# Usb_Hub-EasyEdaPro_Project.net
KiCad netlist of a schematic drawn in EasyEDA Pro
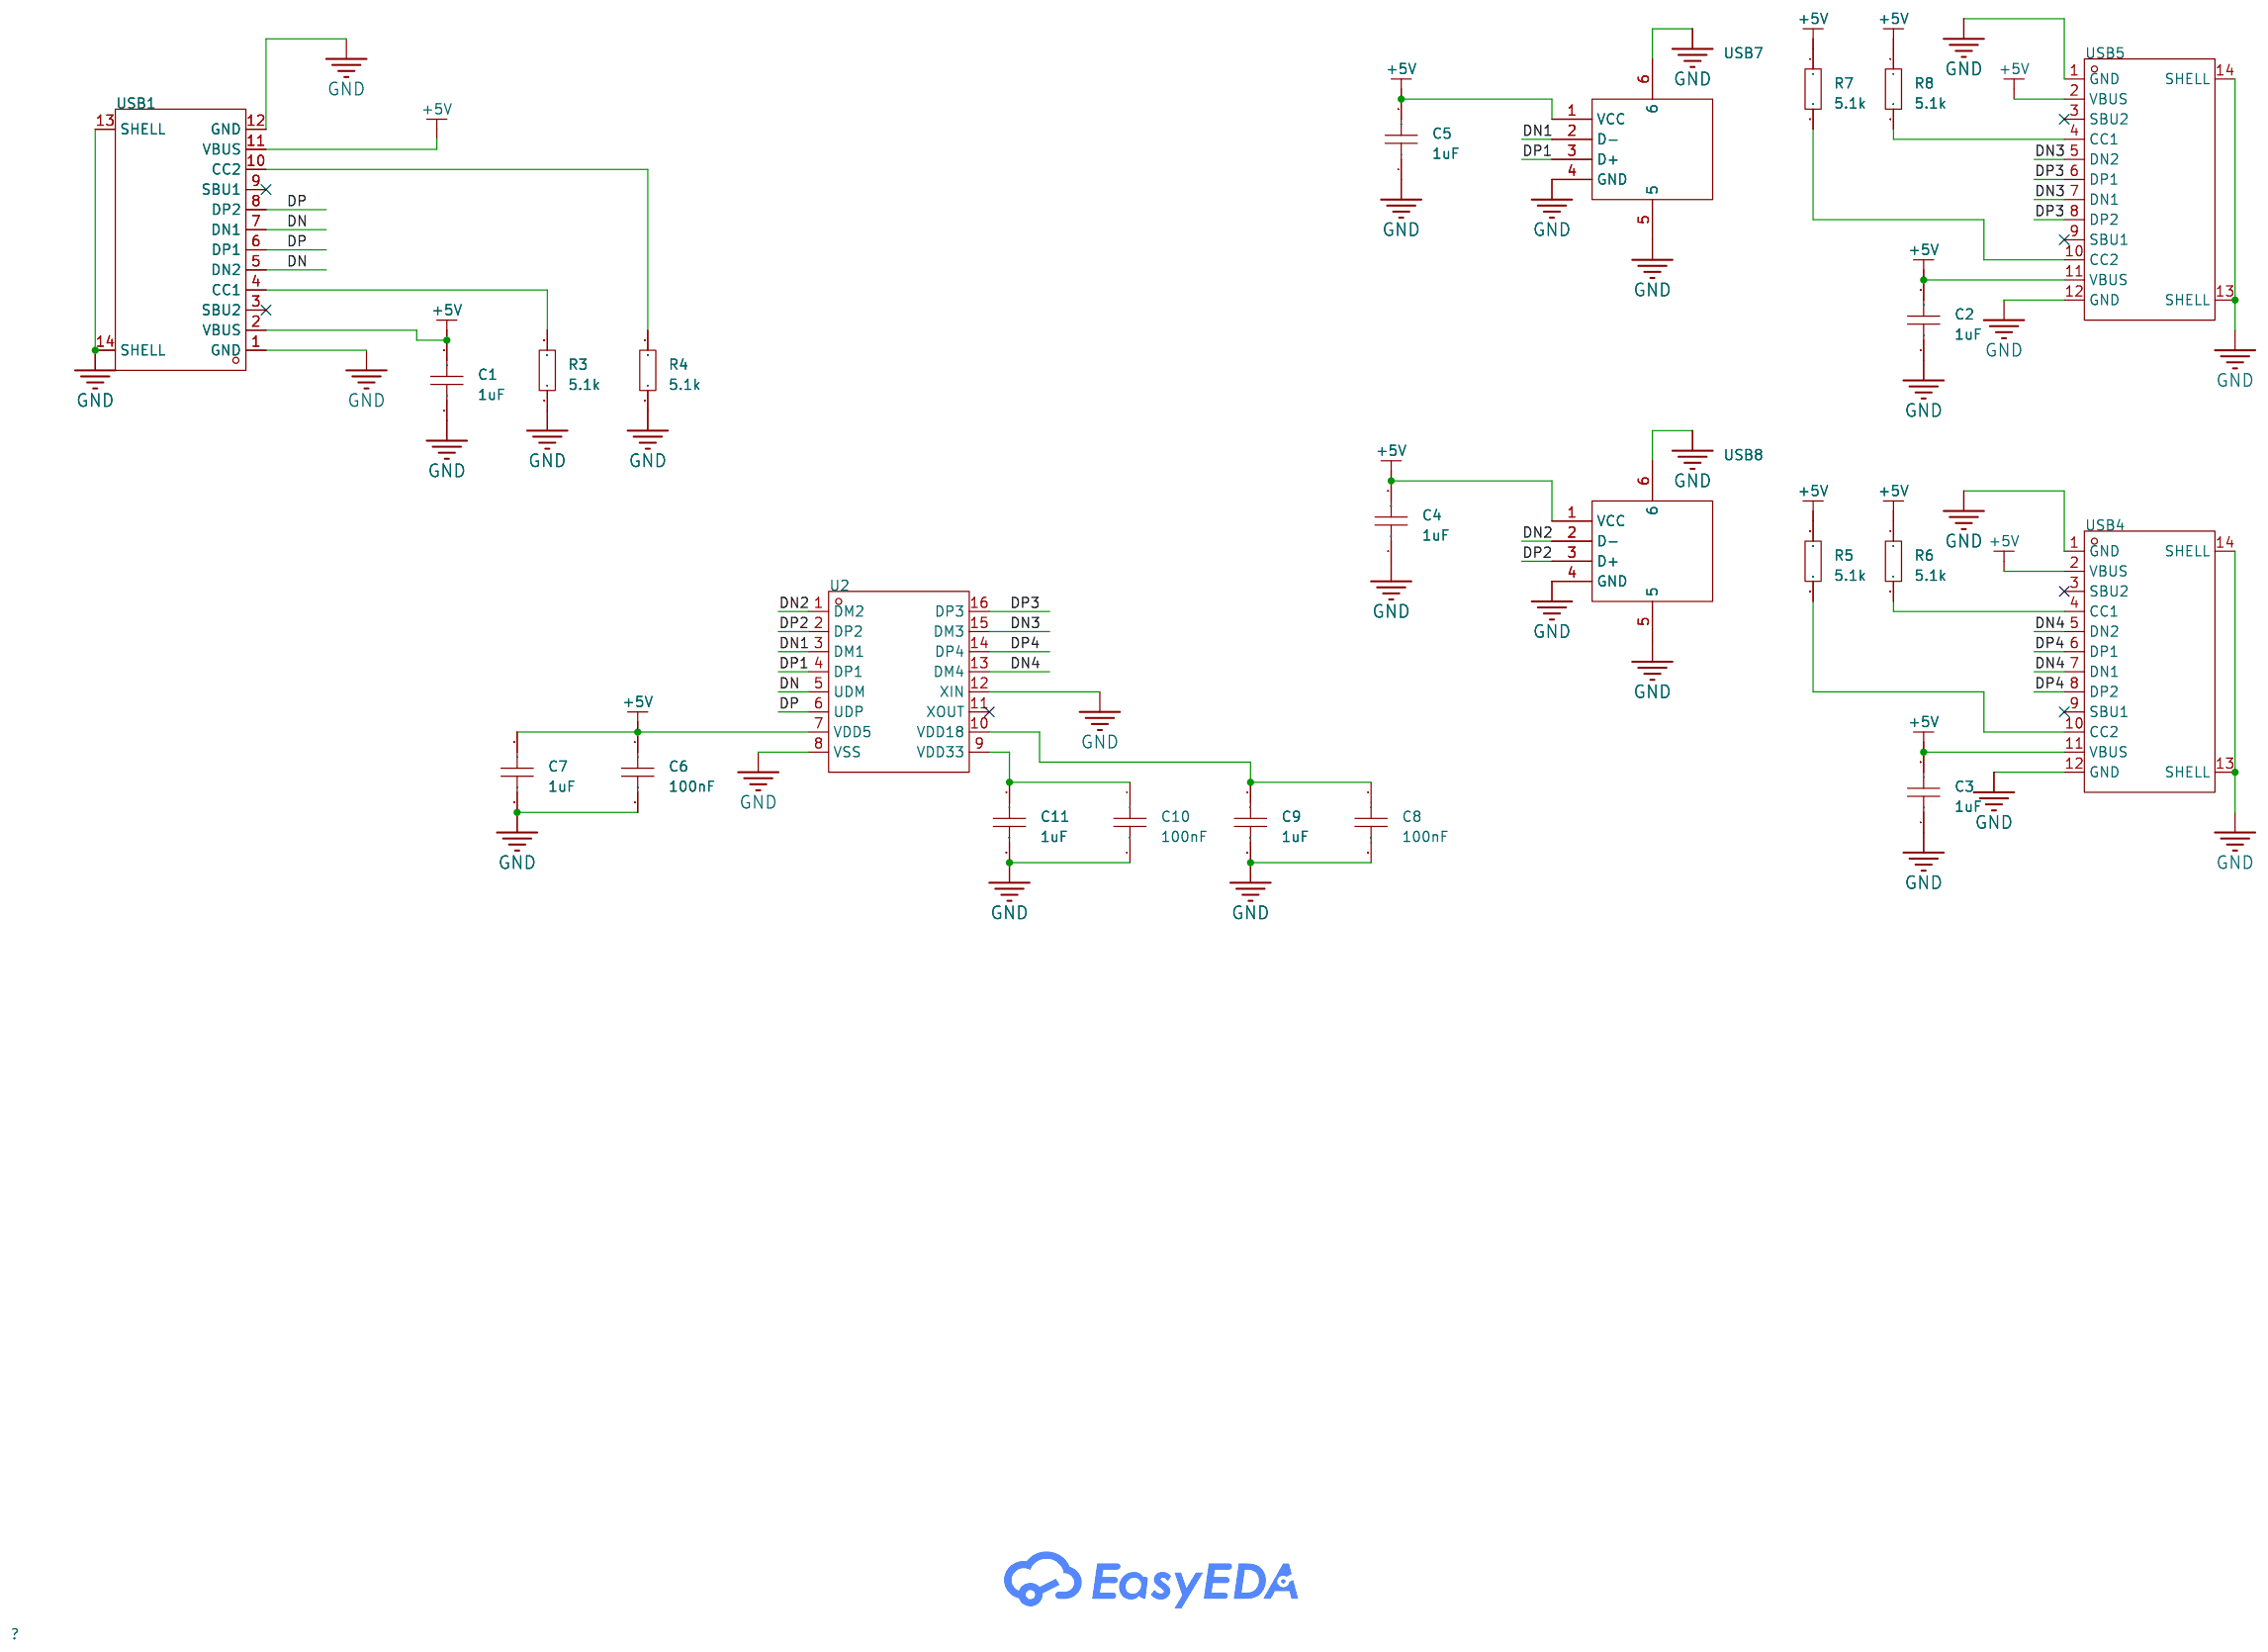
[diagram p0: schematic sheet]

(export (version "E")
  (design (tool "Eeschema 10.0.6"))
  (components
    (comp (ref "C1") (value "1uF") (footprint "easyedapro:C0603") (libsource (lib "easyedapro") (part "CAP")))
    (comp (ref "C2") (value "1uF") (footprint "easyedapro:C0603") (libsource (lib "easyedapro") (part "CAP")))
    (comp (ref "C3") (value "1uF") (footprint "easyedapro:C0603") (libsource (lib "easyedapro") (part "CAP")))
    (comp (ref "C4") (value "1uF") (footprint "easyedapro:C0603") (libsource (lib "easyedapro") (part "CAP")))
    (comp (ref "C5") (value "1uF") (footprint "easyedapro:C0603") (libsource (lib "easyedapro") (part "CAP")))
    (comp (ref "C6")
      (value "100nF")
      (footprint "easyedapro:C0603")
      (libsource (lib "easyedapro") (part "CAP"))
    )
    (comp (ref "C7") (value "1uF") (footprint "easyedapro:C0603") (libsource (lib "easyedapro") (part "CAP")))
    (comp (ref "C8")
      (value "100nF")
      (footprint "easyedapro:C0603")
      (libsource (lib "easyedapro") (part "CAP"))
    )
    (comp (ref "C9") (value "1uF") (footprint "easyedapro:C0603") (libsource (lib "easyedapro") (part "CAP")))
    (comp (ref "C10")
      (value "100nF")
      (footprint "easyedapro:C0603")
      (libsource (lib "easyedapro") (part "CAP"))
    )
    (comp (ref "C11")
      (value "1uF")
      (footprint "easyedapro:C0603")
      (libsource (lib "easyedapro") (part "CAP"))
    )
    (comp (ref "R3")
      (value "5.1k")
      (footprint "easyedapro:R0603")
      (libsource (lib "easyedapro") (part "Res"))
    )
    (comp (ref "R4")
      (value "5.1k")
      (footprint "easyedapro:R0603")
      (libsource (lib "easyedapro") (part "Res"))
    )
    (comp (ref "R5")
      (value "5.1k")
      (footprint "easyedapro:R0603")
      (libsource (lib "easyedapro") (part "Res"))
    )
    (comp (ref "R6")
      (value "5.1k")
      (footprint "easyedapro:R0603")
      (libsource (lib "easyedapro") (part "Res"))
    )
    (comp (ref "R7")
      (value "5.1k")
      (footprint "easyedapro:R0603")
      (libsource (lib "easyedapro") (part "Res"))
    )
    (comp (ref "R8")
      (value "5.1k")
      (footprint "easyedapro:R0603")
      (libsource (lib "easyedapro") (part "Res"))
    )
    (comp (ref "U2")
      (value "SL2.1s")
      (footprint "easyedapro:SSOP-16_L4.6-W2.6-P0.53-LS4.0-BL")
      (fields (field (name "Manufacturer") "CoreChips(和芯润德)"))
      (libsource (lib "easyedapro") (part "SL2.1S"))
    )
    (comp (ref "USB1")
      (value "TYPE-C 16PIN 2MD(073)")
      (footprint "easyedapro:USB-C-SMD_TYPE-C-6PIN-2MD-073")
      (fields (field (name "Manufacturer") "SHOU HAN(首韩)"))
      (libsource (lib "easyedapro") (part "TYPE-C 16PIN 2MD(073)"))
    )
    (comp (ref "USB4")
      (value "TYPE-C 16PIN 2MD(073)")
      (footprint "easyedapro:USB-C-SMD_TYPE-C-6PIN-2MD-073")
      (fields (field (name "Manufacturer") "SHOU HAN(首韩)"))
      (libsource (lib "easyedapro") (part "TYPE-C 16PIN 2MD(073)"))
    )
    (comp (ref "USB5")
      (value "TYPE-C 16PIN 2MD(073)")
      (footprint "easyedapro:USB-C-SMD_TYPE-C-6PIN-2MD-073")
      (fields (field (name "Manufacturer") "SHOU HAN(首韩)"))
      (libsource (lib "easyedapro") (part "TYPE-C 16PIN 2MD(073)"))
    )
    (comp (ref "USB7")
      (value "10.0 QHHTZB6.3")
      (footprint "easyedapro:USB-A-TH_10.0QHHTZB6.3")
      (fields (field (name "Manufacturer") "SHOU HAN(首韩)"))
      (libsource (lib "easyedapro") (part "10.0 QHHTZB6.3"))
    )
    (comp (ref "USB8")
      (value "10.0 QHHTZB6.3")
      (footprint "easyedapro:USB-A-TH_10.0QHHTZB6.3")
      (fields (field (name "Manufacturer") "SHOU HAN(首韩)"))
      (libsource (lib "easyedapro") (part "10.0 QHHTZB6.3"))
    )
  )
  (nets
    (net (code "1") (name "+5V") (class "Default")
      (node (ref "C1") (pin "2") (pinfunction "2_2") (pintype "input"))
      (node (ref "C2") (pin "2") (pinfunction "2_2") (pintype "input"))
      (node (ref "C3") (pin "2") (pinfunction "2_2") (pintype "input"))
      (node (ref "C4") (pin "2") (pinfunction "2_2") (pintype "input"))
      (node (ref "C5") (pin "2") (pinfunction "2_2") (pintype "input"))
      (node (ref "C6") (pin "1") (pinfunction "1_1") (pintype "input"))
      (node (ref "C7") (pin "1") (pinfunction "1_1") (pintype "input"))
      (node (ref "R5") (pin "1") (pinfunction "1_1") (pintype "input"))
      (node (ref "R6") (pin "1") (pinfunction "1_1") (pintype "input"))
      (node (ref "R7") (pin "1") (pinfunction "1_1") (pintype "input"))
      (node (ref "R8") (pin "1") (pinfunction "1_1") (pintype "input"))
      (node (ref "U2") (pin "7") (pinfunction "VDD5_7") (pintype "unspecified"))
      (node (ref "USB1") (pin "11") (pinfunction "VBUS_11") (pintype "unspecified"))
      (node (ref "USB1") (pin "2") (pinfunction "VBUS_2") (pintype "unspecified"))
      (node (ref "USB4") (pin "11") (pinfunction "VBUS_11") (pintype "unspecified"))
      (node (ref "USB4") (pin "2") (pinfunction "VBUS_2") (pintype "unspecified"))
      (node (ref "USB5") (pin "11") (pinfunction "VBUS_11") (pintype "unspecified"))
      (node (ref "USB5") (pin "2") (pinfunction "VBUS_2") (pintype "unspecified"))
      (node (ref "USB7") (pin "1") (pinfunction "VCC_1") (pintype "unspecified"))
      (node (ref "USB8") (pin "1") (pinfunction "VCC_1") (pintype "unspecified"))
    )
    (net (code "2") (name "/DN") (class "Default")
      (node (ref "U2") (pin "5") (pinfunction "UDM_5") (pintype "unspecified"))
      (node (ref "USB1") (pin "5") (pinfunction "DN2_5") (pintype "unspecified"))
      (node (ref "USB1") (pin "7") (pinfunction "DN1_7") (pintype "unspecified"))
    )
    (net (code "3") (name "/DN1") (class "Default")
      (node (ref "U2") (pin "3") (pinfunction "DM1_3") (pintype "unspecified"))
      (node (ref "USB7") (pin "2") (pinfunction "D-_2") (pintype "unspecified"))
    )
    (net (code "4") (name "/DN2") (class "Default")
      (node (ref "U2") (pin "1") (pinfunction "DM2_1") (pintype "unspecified"))
      (node (ref "USB8") (pin "2") (pinfunction "D-_2") (pintype "unspecified"))
    )
    (net (code "5") (name "/DN3") (class "Default")
      (node (ref "U2") (pin "15") (pinfunction "DM3_15") (pintype "unspecified"))
      (node (ref "USB5") (pin "5") (pinfunction "DN2_5") (pintype "unspecified"))
      (node (ref "USB5") (pin "7") (pinfunction "DN1_7") (pintype "unspecified"))
    )
    (net (code "6") (name "/DN4") (class "Default")
      (node (ref "U2") (pin "13") (pinfunction "DM4_13") (pintype "unspecified"))
      (node (ref "USB4") (pin "5") (pinfunction "DN2_5") (pintype "unspecified"))
      (node (ref "USB4") (pin "7") (pinfunction "DN1_7") (pintype "unspecified"))
    )
    (net (code "7") (name "/DP") (class "Default")
      (node (ref "U2") (pin "6") (pinfunction "UDP_6") (pintype "unspecified"))
      (node (ref "USB1") (pin "6") (pinfunction "DP1_6") (pintype "unspecified"))
      (node (ref "USB1") (pin "8") (pinfunction "DP2_8") (pintype "unspecified"))
    )
    (net (code "8") (name "/DP1") (class "Default")
      (node (ref "U2") (pin "4") (pinfunction "DP1_4") (pintype "unspecified"))
      (node (ref "USB7") (pin "3") (pinfunction "D+_3") (pintype "unspecified"))
    )
    (net (code "9") (name "/DP2") (class "Default")
      (node (ref "U2") (pin "2") (pinfunction "DP2_2") (pintype "unspecified"))
      (node (ref "USB8") (pin "3") (pinfunction "D+_3") (pintype "unspecified"))
    )
    (net (code "10") (name "/DP3") (class "Default")
      (node (ref "U2") (pin "16") (pinfunction "DP3_16") (pintype "unspecified"))
      (node (ref "USB5") (pin "6") (pinfunction "DP1_6") (pintype "unspecified"))
      (node (ref "USB5") (pin "8") (pinfunction "DP2_8") (pintype "unspecified"))
    )
    (net (code "11") (name "/DP4") (class "Default")
      (node (ref "U2") (pin "14") (pinfunction "DP4_14") (pintype "unspecified"))
      (node (ref "USB4") (pin "6") (pinfunction "DP1_6") (pintype "unspecified"))
      (node (ref "USB4") (pin "8") (pinfunction "DP2_8") (pintype "unspecified"))
    )
    (net (code "12") (name "GND") (class "Default")
      (node (ref "C1") (pin "1") (pinfunction "1_1") (pintype "input"))
      (node (ref "C10") (pin "2") (pinfunction "2_2") (pintype "input"))
      (node (ref "C11") (pin "2") (pinfunction "2_2") (pintype "input"))
      (node (ref "C2") (pin "1") (pinfunction "1_1") (pintype "input"))
      (node (ref "C3") (pin "1") (pinfunction "1_1") (pintype "input"))
      (node (ref "C4") (pin "1") (pinfunction "1_1") (pintype "input"))
      (node (ref "C5") (pin "1") (pinfunction "1_1") (pintype "input"))
      (node (ref "C6") (pin "2") (pinfunction "2_2") (pintype "input"))
      (node (ref "C7") (pin "2") (pinfunction "2_2") (pintype "input"))
      (node (ref "C8") (pin "2") (pinfunction "2_2") (pintype "input"))
      (node (ref "C9") (pin "2") (pinfunction "2_2") (pintype "input"))
      (node (ref "R3") (pin "1") (pinfunction "1_1") (pintype "input"))
      (node (ref "R4") (pin "1") (pinfunction "1_1") (pintype "input"))
      (node (ref "U2") (pin "12") (pinfunction "XIN_12") (pintype "unspecified"))
      (node (ref "U2") (pin "8") (pinfunction "VSS_8") (pintype "unspecified"))
      (node (ref "USB1") (pin "1") (pinfunction "GND_1") (pintype "unspecified"))
      (node (ref "USB1") (pin "12") (pinfunction "GND_12") (pintype "unspecified"))
      (node (ref "USB1") (pin "13") (pinfunction "SHELL_13") (pintype "unspecified"))
      (node (ref "USB1") (pin "14") (pinfunction "SHELL_14") (pintype "unspecified"))
      (node (ref "USB4") (pin "1") (pinfunction "GND_1") (pintype "unspecified"))
      (node (ref "USB4") (pin "12") (pinfunction "GND_12") (pintype "unspecified"))
      (node (ref "USB4") (pin "13") (pinfunction "SHELL_13") (pintype "unspecified"))
      (node (ref "USB4") (pin "14") (pinfunction "SHELL_14") (pintype "unspecified"))
      (node (ref "USB5") (pin "1") (pinfunction "GND_1") (pintype "unspecified"))
      (node (ref "USB5") (pin "12") (pinfunction "GND_12") (pintype "unspecified"))
      (node (ref "USB5") (pin "13") (pinfunction "SHELL_13") (pintype "unspecified"))
      (node (ref "USB5") (pin "14") (pinfunction "SHELL_14") (pintype "unspecified"))
      (node (ref "USB7") (pin "4") (pinfunction "GND_4") (pintype "unspecified"))
      (node (ref "USB7") (pin "5") (pinfunction "5_5") (pintype "unspecified"))
      (node (ref "USB7") (pin "6") (pinfunction "6_6") (pintype "unspecified"))
      (node (ref "USB8") (pin "4") (pinfunction "GND_4") (pintype "unspecified"))
      (node (ref "USB8") (pin "5") (pinfunction "5_5") (pintype "unspecified"))
      (node (ref "USB8") (pin "6") (pinfunction "6_6") (pintype "unspecified"))
    )
    (net (code "13") (name "Net-(U2-VDD18)") (class "Default")
      (node (ref "C8") (pin "1") (pinfunction "1_1") (pintype "input"))
      (node (ref "C9") (pin "1") (pinfunction "1_1") (pintype "input"))
      (node (ref "U2") (pin "10") (pinfunction "VDD18_10") (pintype "unspecified"))
    )
    (net (code "14") (name "Net-(U2-VDD33)") (class "Default")
      (node (ref "C10") (pin "1") (pinfunction "1_1") (pintype "input"))
      (node (ref "C11") (pin "1") (pinfunction "1_1") (pintype "input"))
      (node (ref "U2") (pin "9") (pinfunction "VDD33_9") (pintype "unspecified"))
    )
    (net (code "15") (name "Net-(USB1-CC1)") (class "Default")
      (node (ref "R3") (pin "2") (pinfunction "2_2") (pintype "input"))
      (node (ref "USB1") (pin "4") (pinfunction "CC1_4") (pintype "unspecified"))
    )
    (net (code "16") (name "Net-(USB1-CC2)") (class "Default")
      (node (ref "R4") (pin "2") (pinfunction "2_2") (pintype "input"))
      (node (ref "USB1") (pin "10") (pinfunction "CC2_10") (pintype "unspecified"))
    )
    (net (code "17") (name "Net-(USB4-CC1)") (class "Default")
      (node (ref "R6") (pin "2") (pinfunction "2_2") (pintype "input"))
      (node (ref "USB4") (pin "4") (pinfunction "CC1_4") (pintype "unspecified"))
    )
    (net (code "18") (name "Net-(USB4-CC2)") (class "Default")
      (node (ref "R5") (pin "2") (pinfunction "2_2") (pintype "input"))
      (node (ref "USB4") (pin "10") (pinfunction "CC2_10") (pintype "unspecified"))
    )
    (net (code "19") (name "Net-(USB5-CC1)") (class "Default")
      (node (ref "R8") (pin "2") (pinfunction "2_2") (pintype "input"))
      (node (ref "USB5") (pin "4") (pinfunction "CC1_4") (pintype "unspecified"))
    )
    (net (code "20") (name "Net-(USB5-CC2)") (class "Default")
      (node (ref "R7") (pin "2") (pinfunction "2_2") (pintype "input"))
      (node (ref "USB5") (pin "10") (pinfunction "CC2_10") (pintype "unspecified"))
    )
    (net (code "21") (name "unconnected-(U2-XOUT-Pad11)") (class "Default")
      (node (ref "U2") (pin "11") (pinfunction "XOUT_11") (pintype "unspecified+no_connect"))
    )
    (net (code "22") (name "unconnected-(USB1-SBU1-Pad9)") (class "Default")
      (node (ref "USB1") (pin "9") (pinfunction "SBU1_9") (pintype "unspecified+no_connect"))
    )
    (net (code "23") (name "unconnected-(USB1-SBU2-Pad3)") (class "Default")
      (node (ref "USB1") (pin "3") (pinfunction "SBU2_3") (pintype "unspecified+no_connect"))
    )
    (net (code "24") (name "unconnected-(USB4-SBU1-Pad9)") (class "Default")
      (node (ref "USB4") (pin "9") (pinfunction "SBU1_9") (pintype "unspecified+no_connect"))
    )
    (net (code "25") (name "unconnected-(USB4-SBU2-Pad3)") (class "Default")
      (node (ref "USB4") (pin "3") (pinfunction "SBU2_3") (pintype "unspecified+no_connect"))
    )
    (net (code "26") (name "unconnected-(USB5-SBU1-Pad9)") (class "Default")
      (node (ref "USB5") (pin "9") (pinfunction "SBU1_9") (pintype "unspecified+no_connect"))
    )
    (net (code "27") (name "unconnected-(USB5-SBU2-Pad3)") (class "Default")
      (node (ref "USB5") (pin "3") (pinfunction "SBU2_3") (pintype "unspecified+no_connect"))
    )
  )
)
